# nanoHC06Rx.net
KiCad netlist of a schematic drawn in EAGLE
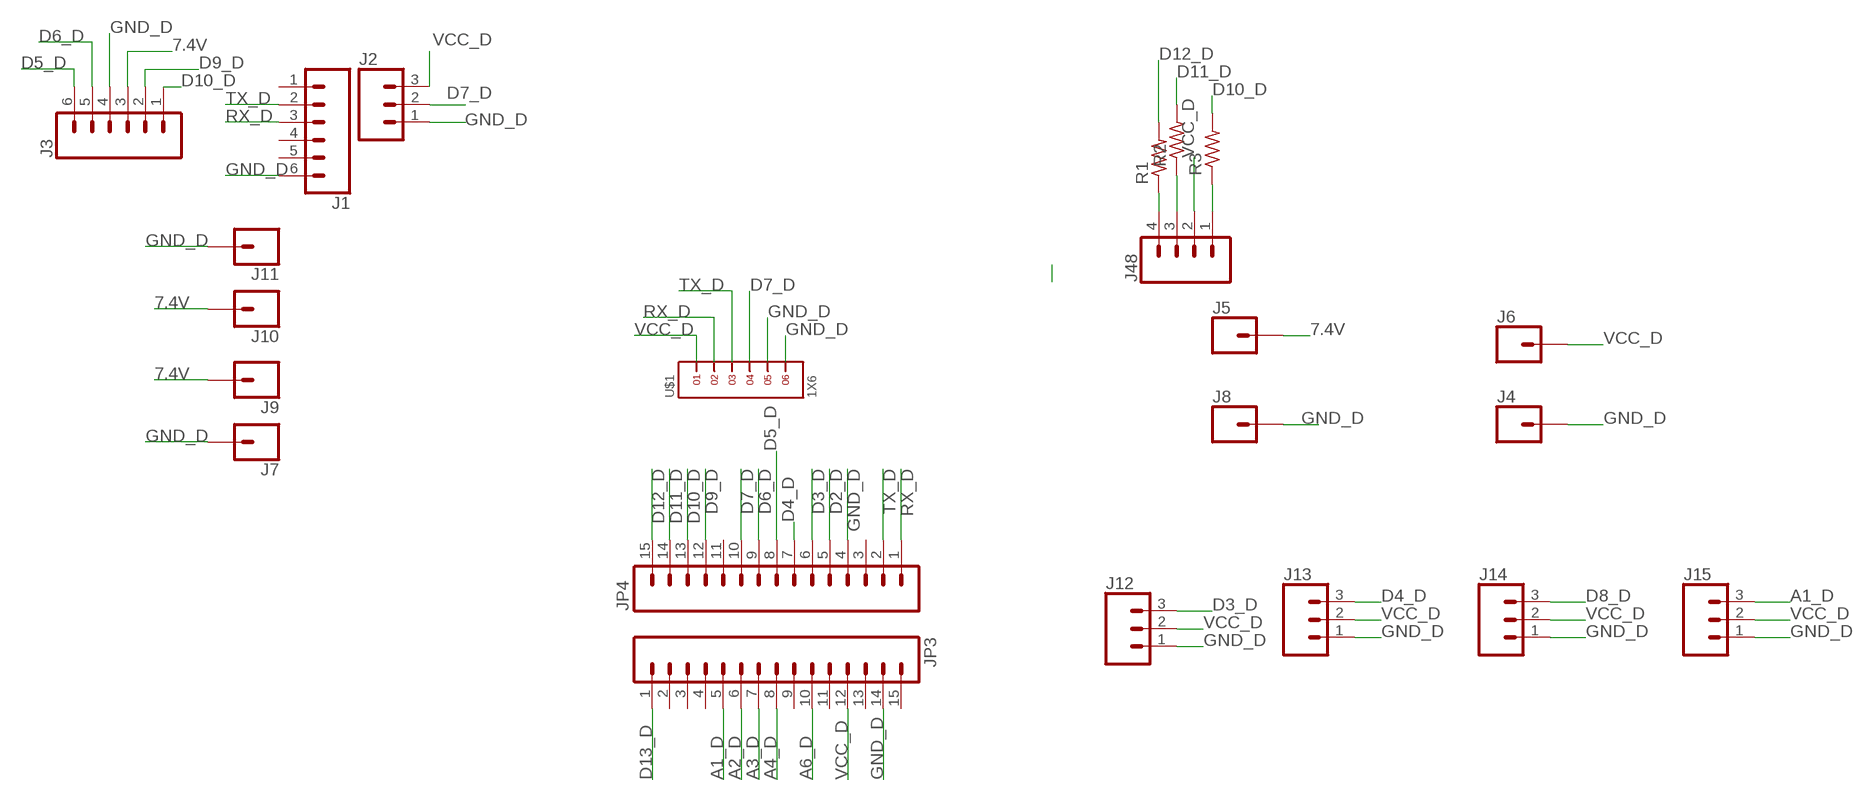
[diagram p0: schematic, sheet 1]

(export (version "E")
  (design (tool "Eeschema 10.0.6"))
  (components
    (comp (ref "J1")
      (value "CONN_06SILK_FEMALE_PTH")
      (footprint "eagle-import:1X06")
      (libsource (lib "eagle-import") (part "CONN_06SILK_FEMALE_PTH"))
    )
    (comp (ref "J2")
      (value "CONN_03")
      (footprint "eagle-import:1X03")
      (libsource (lib "eagle-import") (part "CONN_03"))
    )
    (comp (ref "J3")
      (value "CONN_06SILK_FEMALE_PTH")
      (footprint "eagle-import:1X06")
      (libsource (lib "eagle-import") (part "CONN_06SILK_FEMALE_PTH"))
    )
    (comp (ref "J4")
      (value "CONN_01")
      (footprint "eagle-import:1X01")
      (libsource (lib "eagle-import") (part "CONN_01"))
    )
    (comp (ref "J5")
      (value "CONN_01")
      (footprint "eagle-import:1X01")
      (libsource (lib "eagle-import") (part "CONN_01"))
    )
    (comp (ref "J6")
      (value "CONN_01")
      (footprint "eagle-import:1X01")
      (libsource (lib "eagle-import") (part "CONN_01"))
    )
    (comp (ref "J7")
      (value "CONN_01")
      (footprint "eagle-import:1X01")
      (libsource (lib "eagle-import") (part "CONN_01"))
    )
    (comp (ref "J8")
      (value "CONN_01")
      (footprint "eagle-import:1X01")
      (libsource (lib "eagle-import") (part "CONN_01"))
    )
    (comp (ref "J9")
      (value "CONN_01")
      (footprint "eagle-import:1X01")
      (libsource (lib "eagle-import") (part "CONN_01"))
    )
    (comp (ref "J10")
      (value "CONN_01")
      (footprint "eagle-import:1X01")
      (libsource (lib "eagle-import") (part "CONN_01"))
    )
    (comp (ref "J11")
      (value "CONN_01")
      (footprint "eagle-import:1X01")
      (libsource (lib "eagle-import") (part "CONN_01"))
    )
    (comp (ref "J12")
      (value "CONN_03")
      (footprint "eagle-import:1X03")
      (libsource (lib "eagle-import") (part "CONN_03"))
    )
    (comp (ref "J13")
      (value "CONN_03")
      (footprint "eagle-import:1X03")
      (libsource (lib "eagle-import") (part "CONN_03"))
    )
    (comp (ref "J14")
      (value "CONN_03")
      (footprint "eagle-import:1X03")
      (libsource (lib "eagle-import") (part "CONN_03"))
    )
    (comp (ref "J15")
      (value "CONN_03")
      (footprint "eagle-import:1X03")
      (libsource (lib "eagle-import") (part "CONN_03"))
    )
    (comp (ref "J48")
      (value "CONN_04")
      (footprint "eagle-import:1X04")
      (libsource (lib "eagle-import") (part "CONN_04"))
    )
    (comp (ref "JP3")
      (value "M15")
      (footprint "eagle-import:1X15@1")
      (libsource (lib "eagle-import") (part "M15"))
    )
    (comp (ref "JP4")
      (value "M15")
      (footprint "eagle-import:1X15@1")
      (libsource (lib "eagle-import") (part "M15"))
    )
    (comp (ref "R1")
      (value "R-US_0309/10")
      (footprint "eagle-import:0309_10")
      (libsource (lib "eagle-import") (part "R-US_0309/10"))
    )
    (comp (ref "R2")
      (value "R-US_0309/10")
      (footprint "eagle-import:0309_10")
      (libsource (lib "eagle-import") (part "R-US_0309/10"))
    )
    (comp (ref "R3")
      (value "R-US_0309/10")
      (footprint "eagle-import:0309_10")
      (libsource (lib "eagle-import") (part "R-US_0309/10"))
    )
    (comp (ref "U$1")
      (value "1X6")
      (footprint "eagle-import:1X6")
      (libsource (lib "eagle-import") (part "1X6"))
    )
  )
  (nets
    (net (code "1") (name "/7.4V") (class "Default")
      (node (ref "J10") (pin "1") (pinfunction "1_1") (pintype "passive"))
      (node (ref "J3") (pin "3") (pinfunction "3_3") (pintype "passive"))
      (node (ref "J5") (pin "1") (pinfunction "1_1") (pintype "passive"))
      (node (ref "J9") (pin "1") (pinfunction "1_1") (pintype "passive"))
    )
    (net (code "2") (name "/A1_D") (class "Default")
      (node (ref "J15") (pin "3") (pinfunction "3_3") (pintype "passive"))
      (node (ref "JP3") (pin "5") (pinfunction "5_5") (pintype "passive"))
    )
    (net (code "3") (name "/A2_D") (class "Default")
      (node (ref "JP3") (pin "6") (pinfunction "6_6") (pintype "passive"))
    )
    (net (code "4") (name "/A3_D") (class "Default")
      (node (ref "JP3") (pin "7") (pinfunction "7_7") (pintype "passive"))
    )
    (net (code "5") (name "/A4_D") (class "Default")
      (node (ref "JP3") (pin "8") (pinfunction "8_8") (pintype "passive"))
    )
    (net (code "6") (name "/A6_D") (class "Default")
      (node (ref "JP3") (pin "10") (pinfunction "10_10") (pintype "passive"))
    )
    (net (code "7") (name "/D2_D") (class "Default")
      (node (ref "JP4") (pin "5") (pinfunction "5_5") (pintype "passive"))
    )
    (net (code "8") (name "/D3_D") (class "Default")
      (node (ref "J12") (pin "3") (pinfunction "3_3") (pintype "passive"))
      (node (ref "JP4") (pin "6") (pinfunction "6_6") (pintype "passive"))
    )
    (net (code "9") (name "/D4_D") (class "Default")
      (node (ref "J13") (pin "3") (pinfunction "3_3") (pintype "passive"))
      (node (ref "JP4") (pin "7") (pinfunction "7_7") (pintype "passive"))
    )
    (net (code "10") (name "/D5_D") (class "Default")
      (node (ref "J3") (pin "6") (pinfunction "6_6") (pintype "passive"))
      (node (ref "JP4") (pin "8") (pinfunction "8_8") (pintype "passive"))
    )
    (net (code "11") (name "/D6_D") (class "Default")
      (node (ref "J3") (pin "5") (pinfunction "5_5") (pintype "passive"))
      (node (ref "JP4") (pin "9") (pinfunction "9_9") (pintype "passive"))
    )
    (net (code "12") (name "/D7_D") (class "Default")
      (node (ref "J2") (pin "2") (pinfunction "2_2") (pintype "passive"))
      (node (ref "JP4") (pin "10") (pinfunction "10_10") (pintype "passive"))
      (node (ref "U$1") (pin "4") (pinfunction "4_4") (pintype "bidirectional"))
    )
    (net (code "13") (name "/D8_D") (class "Default")
      (node (ref "J14") (pin "3") (pinfunction "3_3") (pintype "passive"))
    )
    (net (code "14") (name "/D9_D") (class "Default")
      (node (ref "J3") (pin "2") (pinfunction "2_2") (pintype "passive"))
      (node (ref "JP4") (pin "12") (pinfunction "12_12") (pintype "passive"))
    )
    (net (code "15") (name "/D10_D") (class "Default")
      (node (ref "J3") (pin "1") (pinfunction "1_1") (pintype "passive"))
      (node (ref "JP4") (pin "13") (pinfunction "13_13") (pintype "passive"))
      (node (ref "R3") (pin "2") (pinfunction "2_2") (pintype "passive"))
    )
    (net (code "16") (name "/D11_D") (class "Default")
      (node (ref "JP4") (pin "14") (pinfunction "14_14") (pintype "passive"))
      (node (ref "R2") (pin "2") (pinfunction "2_2") (pintype "passive"))
    )
    (net (code "17") (name "/D12_D") (class "Default")
      (node (ref "JP4") (pin "15") (pinfunction "15_15") (pintype "passive"))
      (node (ref "R1") (pin "2") (pinfunction "2_2") (pintype "passive"))
    )
    (net (code "18") (name "/D13_D") (class "Default")
      (node (ref "JP3") (pin "1") (pinfunction "1_1") (pintype "passive"))
    )
    (net (code "19") (name "/GND_D") (class "Default")
      (node (ref "J1") (pin "6") (pinfunction "6_6") (pintype "passive"))
      (node (ref "J11") (pin "1") (pinfunction "1_1") (pintype "passive"))
      (node (ref "J12") (pin "1") (pinfunction "1_1") (pintype "passive"))
      (node (ref "J13") (pin "1") (pinfunction "1_1") (pintype "passive"))
      (node (ref "J14") (pin "1") (pinfunction "1_1") (pintype "passive"))
      (node (ref "J15") (pin "1") (pinfunction "1_1") (pintype "passive"))
      (node (ref "J2") (pin "1") (pinfunction "1_1") (pintype "passive"))
      (node (ref "J3") (pin "4") (pinfunction "4_4") (pintype "passive"))
      (node (ref "J4") (pin "1") (pinfunction "1_1") (pintype "passive"))
      (node (ref "J7") (pin "1") (pinfunction "1_1") (pintype "passive"))
      (node (ref "J8") (pin "1") (pinfunction "1_1") (pintype "passive"))
      (node (ref "JP3") (pin "14") (pinfunction "14_14") (pintype "passive"))
      (node (ref "JP4") (pin "4") (pinfunction "4_4") (pintype "passive"))
      (node (ref "U$1") (pin "5") (pinfunction "5_5") (pintype "bidirectional"))
      (node (ref "U$1") (pin "6") (pinfunction "6_6") (pintype "bidirectional"))
    )
    (net (code "20") (name "/RX_D") (class "Default")
      (node (ref "J1") (pin "3") (pinfunction "3_3") (pintype "passive"))
      (node (ref "JP4") (pin "1") (pinfunction "1_1") (pintype "passive"))
      (node (ref "U$1") (pin "2") (pinfunction "2_2") (pintype "bidirectional"))
    )
    (net (code "21") (name "/TX_D") (class "Default")
      (node (ref "J1") (pin "2") (pinfunction "2_2") (pintype "passive"))
      (node (ref "JP4") (pin "2") (pinfunction "2_2") (pintype "passive"))
      (node (ref "U$1") (pin "3") (pinfunction "3_3") (pintype "bidirectional"))
    )
    (net (code "22") (name "/VCC_D") (class "Default")
      (node (ref "J12") (pin "2") (pinfunction "2_2") (pintype "passive"))
      (node (ref "J13") (pin "2") (pinfunction "2_2") (pintype "passive"))
      (node (ref "J14") (pin "2") (pinfunction "2_2") (pintype "passive"))
      (node (ref "J15") (pin "2") (pinfunction "2_2") (pintype "passive"))
      (node (ref "J2") (pin "3") (pinfunction "3_3") (pintype "passive"))
      (node (ref "J48") (pin "2") (pinfunction "2_2") (pintype "passive"))
      (node (ref "J6") (pin "1") (pinfunction "1_1") (pintype "passive"))
      (node (ref "JP3") (pin "12") (pinfunction "12_12") (pintype "passive"))
      (node (ref "U$1") (pin "1") (pinfunction "1_1") (pintype "bidirectional"))
    )
    (net (code "23") (name "Net-(J48-Pad1)") (class "Default")
      (node (ref "J48") (pin "1") (pinfunction "1_1") (pintype "passive"))
      (node (ref "R3") (pin "1") (pinfunction "1_1") (pintype "passive"))
    )
    (net (code "24") (name "Net-(J48-Pad3)") (class "Default")
      (node (ref "J48") (pin "3") (pinfunction "3_3") (pintype "passive"))
      (node (ref "R2") (pin "1") (pinfunction "1_1") (pintype "passive"))
    )
    (net (code "25") (name "Net-(J48-Pad4)") (class "Default")
      (node (ref "J48") (pin "4") (pinfunction "4_4") (pintype "passive"))
      (node (ref "R1") (pin "1") (pinfunction "1_1") (pintype "passive"))
    )
    (net (code "26") (name "unconnected-(J1-Pad1)") (class "Default")
      (node (ref "J1") (pin "1") (pinfunction "1_1") (pintype "passive"))
    )
    (net (code "27") (name "unconnected-(J1-Pad4)") (class "Default")
      (node (ref "J1") (pin "4") (pinfunction "4_4") (pintype "passive"))
    )
    (net (code "28") (name "unconnected-(J1-Pad5)") (class "Default")
      (node (ref "J1") (pin "5") (pinfunction "5_5") (pintype "passive"))
    )
    (net (code "29") (name "unconnected-(JP3-Pad2)") (class "Default")
      (node (ref "JP3") (pin "2") (pinfunction "2_2") (pintype "passive"))
    )
    (net (code "30") (name "unconnected-(JP3-Pad3)") (class "Default")
      (node (ref "JP3") (pin "3") (pinfunction "3_3") (pintype "passive"))
    )
    (net (code "31") (name "unconnected-(JP3-Pad4)") (class "Default")
      (node (ref "JP3") (pin "4") (pinfunction "4_4") (pintype "passive"))
    )
    (net (code "32") (name "unconnected-(JP3-Pad9)") (class "Default")
      (node (ref "JP3") (pin "9") (pinfunction "9_9") (pintype "passive"))
    )
    (net (code "33") (name "unconnected-(JP3-Pad11)") (class "Default")
      (node (ref "JP3") (pin "11") (pinfunction "11_11") (pintype "passive"))
    )
    (net (code "34") (name "unconnected-(JP3-Pad13)") (class "Default")
      (node (ref "JP3") (pin "13") (pinfunction "13_13") (pintype "passive"))
    )
    (net (code "35") (name "unconnected-(JP3-Pad15)") (class "Default")
      (node (ref "JP3") (pin "15") (pinfunction "15_15") (pintype "passive"))
    )
    (net (code "36") (name "unconnected-(JP4-Pad3)") (class "Default")
      (node (ref "JP4") (pin "3") (pinfunction "3_3") (pintype "passive"))
    )
    (net (code "37") (name "unconnected-(JP4-Pad11)") (class "Default")
      (node (ref "JP4") (pin "11") (pinfunction "11_11") (pintype "passive"))
    )
  )
)
